# papilio_cam_board.net
KiCad netlist of a schematic drawn in EAGLE
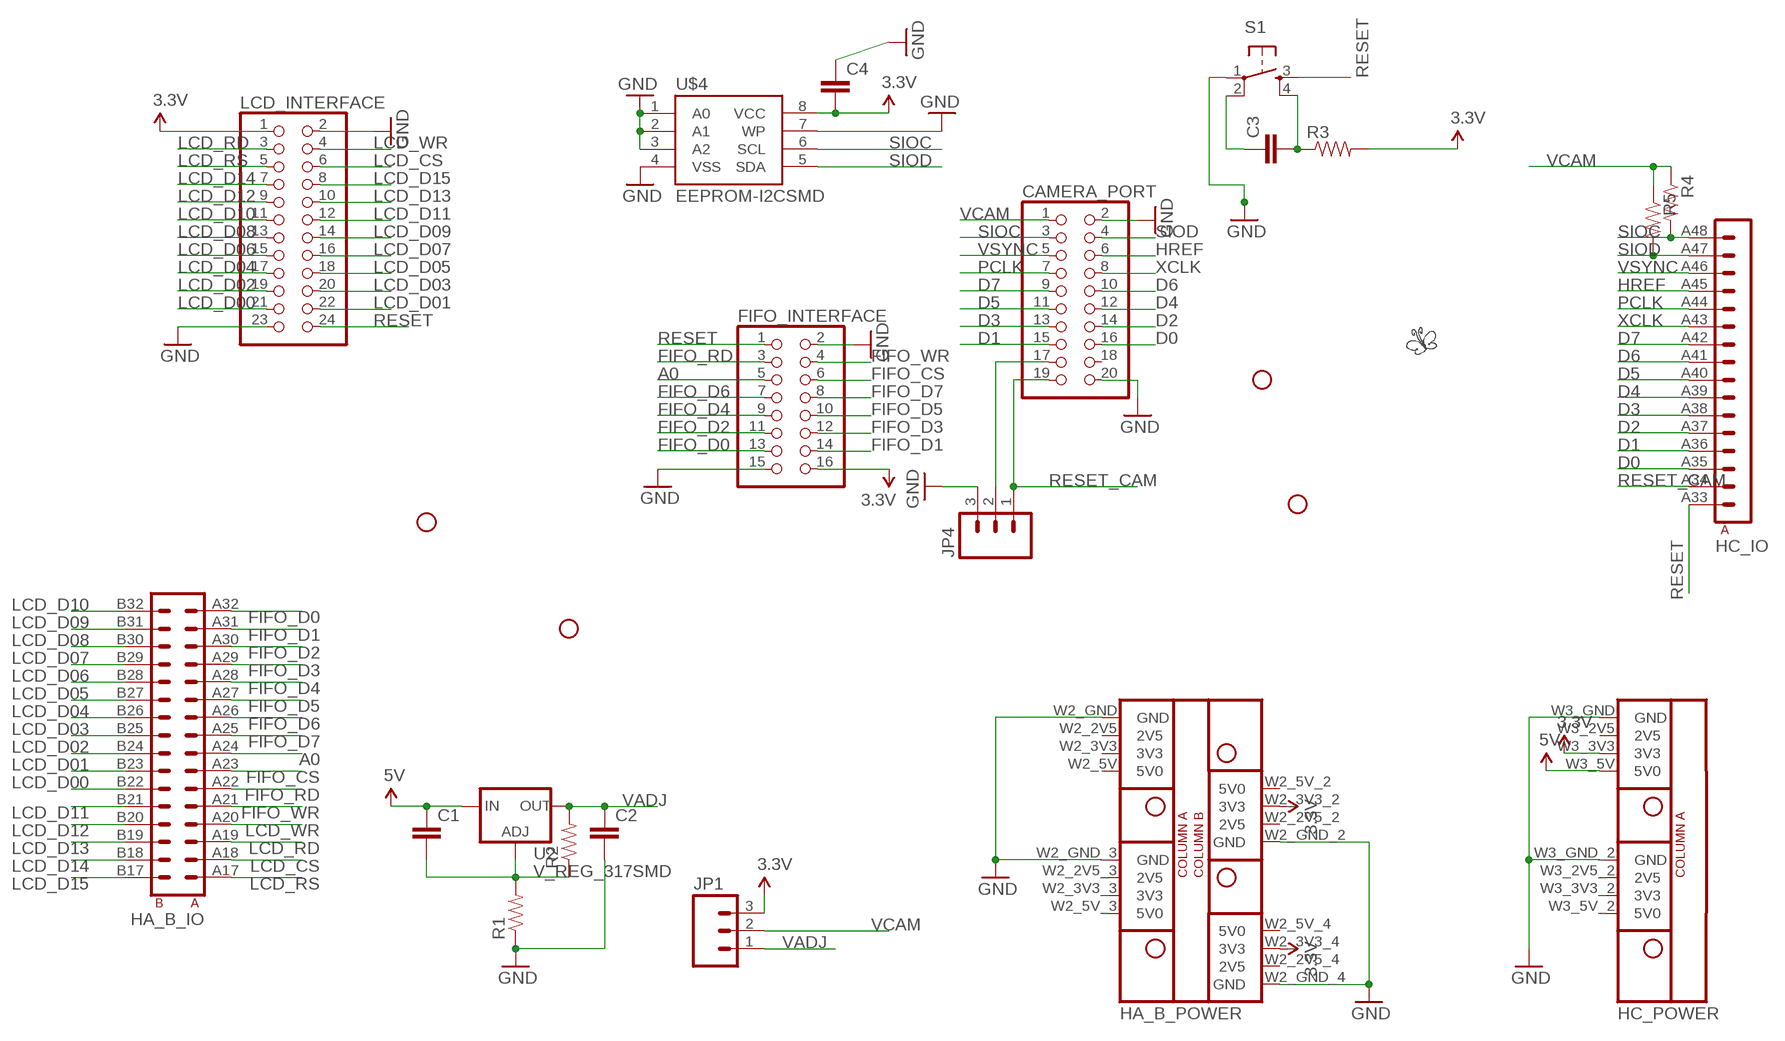
[diagram p0: schematic, sheet 1]

(export (version "E")
  (design (tool "Eeschema 10.0.6"))
  (components
    (comp (ref "C1")
      (value "CAP0805")
      (footprint "eagle-import:0805")
      (libsource (lib "eagle-import") (part "CAP0805"))
    )
    (comp (ref "C2")
      (value "CAP0805")
      (footprint "eagle-import:0805")
      (libsource (lib "eagle-import") (part "CAP0805"))
    )
    (comp (ref "C3")
      (value "CAP0805")
      (footprint "eagle-import:0805")
      (libsource (lib "eagle-import") (part "CAP0805"))
    )
    (comp (ref "C4")
      (value "CAP0805")
      (footprint "eagle-import:0805")
      (libsource (lib "eagle-import") (part "CAP0805"))
    )
    (comp (ref "CAMERA_PORT")
      (value "PINHD-2X10")
      (footprint "eagle-import:2X10")
      (libsource (lib "eagle-import") (part "PINHD-2X10"))
    )
    (comp (ref "FIFO_INTERFACE")
      (value "PINHD-2X8")
      (footprint "eagle-import:2X08")
      (libsource (lib "eagle-import") (part "PINHD-2X8"))
    )
    (comp (ref "H")
      (value "MEGAWING_FULL_P1MEGAWING_P1")
      (footprint "eagle-import:MEGAWING_FULL_NOHOLES_P1")
      (libsource (lib "eagle-import") (part "MEGAWING_FULL_P1MEGAWING_P1"))
    )
    (comp (ref "JP1")
      (value "M03PTH")
      (footprint "eagle-import:1X03")
      (libsource (lib "eagle-import") (part "M03PTH"))
    )
    (comp (ref "JP2")
      (value "STAND-OFF")
      (footprint "eagle-import:STAND-OFF")
      (libsource (lib "eagle-import") (part "STAND-OFF"))
    )
    (comp (ref "JP3")
      (value "STAND-OFF")
      (footprint "eagle-import:STAND-OFF")
      (libsource (lib "eagle-import") (part "STAND-OFF"))
    )
    (comp (ref "JP4")
      (value "M03PTH")
      (footprint "eagle-import:1X03")
      (libsource (lib "eagle-import") (part "M03PTH"))
    )
    (comp (ref "JP5")
      (value "STAND-OFF")
      (footprint "eagle-import:STAND-OFF")
      (libsource (lib "eagle-import") (part "STAND-OFF"))
    )
    (comp (ref "JP7")
      (value "STAND-OFF")
      (footprint "eagle-import:STAND-OFF")
      (libsource (lib "eagle-import") (part "STAND-OFF"))
    )
    (comp (ref "LCD_INTERFACE")
      (value "PINHD-2X12")
      (footprint "eagle-import:2X12")
      (libsource (lib "eagle-import") (part "PINHD-2X12"))
    )
    (comp (ref "LOGO1")
      (value "BUTTERFLY_LOGO")
      (footprint "eagle-import:BUTTERFLY_LOGO")
      (libsource (lib "eagle-import") (part "BUTTERFLY_LOGO"))
    )
    (comp (ref "R1")
      (value "RESISTOR0805-RES")
      (footprint "eagle-import:0805")
      (libsource (lib "eagle-import") (part "RESISTOR0805-RES"))
    )
    (comp (ref "R2")
      (value "RESISTOR0805-RES")
      (footprint "eagle-import:0805")
      (libsource (lib "eagle-import") (part "RESISTOR0805-RES"))
    )
    (comp (ref "R3")
      (value "RESISTOR0805-RES")
      (footprint "eagle-import:0805")
      (libsource (lib "eagle-import") (part "RESISTOR0805-RES"))
    )
    (comp (ref "R4")
      (value "RESISTOR0805-RES")
      (footprint "eagle-import:0805")
      (libsource (lib "eagle-import") (part "RESISTOR0805-RES"))
    )
    (comp (ref "R5")
      (value "RESISTOR0805-RES")
      (footprint "eagle-import:0805")
      (libsource (lib "eagle-import") (part "RESISTOR0805-RES"))
    )
    (comp (ref "S1")
      (value "TAC_SWITCHSMD")
      (footprint "eagle-import:TACTILE_SWITCH_SMD")
      (libsource (lib "eagle-import") (part "TAC_SWITCHSMD"))
    )
    (comp (ref "U$4")
      (value "EEPROM-I2CSMD")
      (footprint "eagle-import:SO08")
      (libsource (lib "eagle-import") (part "EEPROM-I2CSMD"))
    )
    (comp (ref "U2")
      (value "V_REG_317SMD")
      (footprint "eagle-import:SOT223")
      (libsource (lib "eagle-import") (part "V_REG_317SMD"))
    )
  )
  (nets
    (net (code "1") (name "/A0") (class "Default")
      (node (ref "FIFO_INTERFACE") (pin "5") (pinfunction "5_5") (pintype "passive"))
      (node (ref "H") (pin "A24") (pinfunction "A8_A24") (pintype "bidirectional"))
    )
    (net (code "2") (name "/D0") (class "Default")
      (node (ref "CAMERA_PORT") (pin "16") (pinfunction "16_16") (pintype "passive"))
      (node (ref "H") (pin "A35") (pinfunction "A3_A35") (pintype "bidirectional"))
    )
    (net (code "3") (name "/D1") (class "Default")
      (node (ref "CAMERA_PORT") (pin "15") (pinfunction "15_15") (pintype "passive"))
      (node (ref "H") (pin "A36") (pinfunction "A4_A36") (pintype "bidirectional"))
    )
    (net (code "4") (name "/D2") (class "Default")
      (node (ref "CAMERA_PORT") (pin "14") (pinfunction "14_14") (pintype "passive"))
      (node (ref "H") (pin "A37") (pinfunction "A5_A37") (pintype "bidirectional"))
    )
    (net (code "5") (name "/D3") (class "Default")
      (node (ref "CAMERA_PORT") (pin "13") (pinfunction "13_13") (pintype "passive"))
      (node (ref "H") (pin "A38") (pinfunction "A6_A38") (pintype "bidirectional"))
    )
    (net (code "6") (name "/D4") (class "Default")
      (node (ref "CAMERA_PORT") (pin "12") (pinfunction "12_12") (pintype "passive"))
      (node (ref "H") (pin "A39") (pinfunction "A7_A39") (pintype "bidirectional"))
    )
    (net (code "7") (name "/D5") (class "Default")
      (node (ref "CAMERA_PORT") (pin "11") (pinfunction "11_11") (pintype "passive"))
      (node (ref "H") (pin "A40") (pinfunction "A8_A40") (pintype "bidirectional"))
    )
    (net (code "8") (name "/D6") (class "Default")
      (node (ref "CAMERA_PORT") (pin "10") (pinfunction "10_10") (pintype "passive"))
      (node (ref "H") (pin "A41") (pinfunction "A9_A41") (pintype "bidirectional"))
    )
    (net (code "9") (name "/D7") (class "Default")
      (node (ref "CAMERA_PORT") (pin "9") (pinfunction "9_9") (pintype "passive"))
      (node (ref "H") (pin "A42") (pinfunction "A10_A42") (pintype "bidirectional"))
    )
    (net (code "10") (name "/FIFO_CS") (class "Default")
      (node (ref "FIFO_INTERFACE") (pin "6") (pinfunction "6_6") (pintype "passive"))
      (node (ref "H") (pin "A23") (pinfunction "A7_A23") (pintype "bidirectional"))
    )
    (net (code "11") (name "/FIFO_D0") (class "Default")
      (node (ref "FIFO_INTERFACE") (pin "13") (pinfunction "13_13") (pintype "passive"))
      (node (ref "H") (pin "A32") (pinfunction "A16_A32") (pintype "bidirectional"))
    )
    (net (code "12") (name "/FIFO_D1") (class "Default")
      (node (ref "FIFO_INTERFACE") (pin "14") (pinfunction "14_14") (pintype "passive"))
      (node (ref "H") (pin "A31") (pinfunction "A15_A31") (pintype "bidirectional"))
    )
    (net (code "13") (name "/FIFO_D2") (class "Default")
      (node (ref "FIFO_INTERFACE") (pin "11") (pinfunction "11_11") (pintype "passive"))
      (node (ref "H") (pin "A30") (pinfunction "A14_A30") (pintype "bidirectional"))
    )
    (net (code "14") (name "/FIFO_D3") (class "Default")
      (node (ref "FIFO_INTERFACE") (pin "12") (pinfunction "12_12") (pintype "passive"))
      (node (ref "H") (pin "A29") (pinfunction "A13_A29") (pintype "bidirectional"))
    )
    (net (code "15") (name "/FIFO_D4") (class "Default")
      (node (ref "FIFO_INTERFACE") (pin "9") (pinfunction "9_9") (pintype "passive"))
      (node (ref "H") (pin "A28") (pinfunction "A12_A28") (pintype "bidirectional"))
    )
    (net (code "16") (name "/FIFO_D5") (class "Default")
      (node (ref "FIFO_INTERFACE") (pin "10") (pinfunction "10_10") (pintype "passive"))
      (node (ref "H") (pin "A27") (pinfunction "A11_A27") (pintype "bidirectional"))
    )
    (net (code "17") (name "/FIFO_D6") (class "Default")
      (node (ref "FIFO_INTERFACE") (pin "7") (pinfunction "7_7") (pintype "passive"))
      (node (ref "H") (pin "A26") (pinfunction "A10_A26") (pintype "bidirectional"))
    )
    (net (code "18") (name "/FIFO_D7") (class "Default")
      (node (ref "FIFO_INTERFACE") (pin "8") (pinfunction "8_8") (pintype "passive"))
      (node (ref "H") (pin "A25") (pinfunction "A9_A25") (pintype "bidirectional"))
    )
    (net (code "19") (name "/FIFO_RD") (class "Default")
      (node (ref "FIFO_INTERFACE") (pin "3") (pinfunction "3_3") (pintype "passive"))
      (node (ref "H") (pin "A22") (pinfunction "A6_A22") (pintype "bidirectional"))
    )
    (net (code "20") (name "/FIFO_WR") (class "Default")
      (node (ref "FIFO_INTERFACE") (pin "4") (pinfunction "4_4") (pintype "passive"))
      (node (ref "H") (pin "A21") (pinfunction "A5_A21") (pintype "bidirectional"))
    )
    (net (code "21") (name "/HREF") (class "Default")
      (node (ref "CAMERA_PORT") (pin "6") (pinfunction "6_6") (pintype "passive"))
      (node (ref "H") (pin "A45") (pinfunction "A13_A45") (pintype "bidirectional"))
    )
    (net (code "22") (name "/LCD_CS") (class "Default")
      (node (ref "H") (pin "A18") (pinfunction "A2_A18") (pintype "bidirectional"))
      (node (ref "LCD_INTERFACE") (pin "6") (pinfunction "6_6") (pintype "passive"))
    )
    (net (code "23") (name "/LCD_D00") (class "Default")
      (node (ref "H") (pin "B22") (pinfunction "B6_B22") (pintype "bidirectional"))
      (node (ref "LCD_INTERFACE") (pin "21") (pinfunction "21_21") (pintype "passive"))
    )
    (net (code "24") (name "/LCD_D01") (class "Default")
      (node (ref "H") (pin "B23") (pinfunction "B7_B23") (pintype "bidirectional"))
      (node (ref "LCD_INTERFACE") (pin "22") (pinfunction "22_22") (pintype "passive"))
    )
    (net (code "25") (name "/LCD_D02") (class "Default")
      (node (ref "H") (pin "B24") (pinfunction "B8_B24") (pintype "bidirectional"))
      (node (ref "LCD_INTERFACE") (pin "19") (pinfunction "19_19") (pintype "passive"))
    )
    (net (code "26") (name "/LCD_D03") (class "Default")
      (node (ref "H") (pin "B25") (pinfunction "B9_B25") (pintype "bidirectional"))
      (node (ref "LCD_INTERFACE") (pin "20") (pinfunction "20_20") (pintype "passive"))
    )
    (net (code "27") (name "/LCD_D04") (class "Default")
      (node (ref "H") (pin "B26") (pinfunction "B10_B26") (pintype "bidirectional"))
      (node (ref "LCD_INTERFACE") (pin "17") (pinfunction "17_17") (pintype "passive"))
    )
    (net (code "28") (name "/LCD_D05") (class "Default")
      (node (ref "H") (pin "B27") (pinfunction "B11_B27") (pintype "bidirectional"))
      (node (ref "LCD_INTERFACE") (pin "18") (pinfunction "18_18") (pintype "passive"))
    )
    (net (code "29") (name "/LCD_D06") (class "Default")
      (node (ref "H") (pin "B28") (pinfunction "B12_B28") (pintype "bidirectional"))
      (node (ref "LCD_INTERFACE") (pin "15") (pinfunction "15_15") (pintype "passive"))
    )
    (net (code "30") (name "/LCD_D07") (class "Default")
      (node (ref "H") (pin "B29") (pinfunction "B13_B29") (pintype "bidirectional"))
      (node (ref "LCD_INTERFACE") (pin "16") (pinfunction "16_16") (pintype "passive"))
    )
    (net (code "31") (name "/LCD_D08") (class "Default")
      (node (ref "H") (pin "B30") (pinfunction "B14_B30") (pintype "bidirectional"))
      (node (ref "LCD_INTERFACE") (pin "13") (pinfunction "13_13") (pintype "passive"))
    )
    (net (code "32") (name "/LCD_D09") (class "Default")
      (node (ref "H") (pin "B31") (pinfunction "B15_B31") (pintype "bidirectional"))
      (node (ref "LCD_INTERFACE") (pin "14") (pinfunction "14_14") (pintype "passive"))
    )
    (net (code "33") (name "/LCD_D10") (class "Default")
      (node (ref "H") (pin "B32") (pinfunction "B16_B32") (pintype "bidirectional"))
      (node (ref "LCD_INTERFACE") (pin "11") (pinfunction "11_11") (pintype "passive"))
    )
    (net (code "34") (name "/LCD_D11") (class "Default")
      (node (ref "H") (pin "B21") (pinfunction "B5_B21") (pintype "bidirectional"))
      (node (ref "LCD_INTERFACE") (pin "12") (pinfunction "12_12") (pintype "passive"))
    )
    (net (code "35") (name "/LCD_D12") (class "Default")
      (node (ref "H") (pin "B20") (pinfunction "B4_B20") (pintype "bidirectional"))
      (node (ref "LCD_INTERFACE") (pin "9") (pinfunction "9_9") (pintype "passive"))
    )
    (net (code "36") (name "/LCD_D13") (class "Default")
      (node (ref "H") (pin "B19") (pinfunction "B3_B19") (pintype "bidirectional"))
      (node (ref "LCD_INTERFACE") (pin "10") (pinfunction "10_10") (pintype "passive"))
    )
    (net (code "37") (name "/LCD_D14") (class "Default")
      (node (ref "H") (pin "B18") (pinfunction "B2_B18") (pintype "bidirectional"))
      (node (ref "LCD_INTERFACE") (pin "7") (pinfunction "7_7") (pintype "passive"))
    )
    (net (code "38") (name "/LCD_D15") (class "Default")
      (node (ref "H") (pin "B17") (pinfunction "B1_B17") (pintype "bidirectional"))
      (node (ref "LCD_INTERFACE") (pin "8") (pinfunction "8_8") (pintype "passive"))
    )
    (net (code "39") (name "/LCD_RD") (class "Default")
      (node (ref "H") (pin "A19") (pinfunction "A3_A19") (pintype "bidirectional"))
      (node (ref "LCD_INTERFACE") (pin "3") (pinfunction "3_3") (pintype "passive"))
    )
    (net (code "40") (name "/LCD_RS") (class "Default")
      (node (ref "H") (pin "A17") (pinfunction "A1_A17") (pintype "bidirectional"))
      (node (ref "LCD_INTERFACE") (pin "5") (pinfunction "5_5") (pintype "passive"))
    )
    (net (code "41") (name "/LCD_WR") (class "Default")
      (node (ref "H") (pin "A20") (pinfunction "A4_A20") (pintype "bidirectional"))
      (node (ref "LCD_INTERFACE") (pin "4") (pinfunction "4_4") (pintype "passive"))
    )
    (net (code "42") (name "/PCLK") (class "Default")
      (node (ref "CAMERA_PORT") (pin "7") (pinfunction "7_7") (pintype "passive"))
      (node (ref "H") (pin "A44") (pinfunction "A12_A44") (pintype "bidirectional"))
    )
    (net (code "43") (name "/RESET") (class "Default")
      (node (ref "FIFO_INTERFACE") (pin "1") (pinfunction "1_1") (pintype "passive"))
      (node (ref "H") (pin "A33") (pinfunction "A1_A33") (pintype "bidirectional"))
      (node (ref "LCD_INTERFACE") (pin "24") (pinfunction "24_24") (pintype "passive"))
      (node (ref "S1") (pin "3") (pinfunction "3_3") (pintype "passive"))
    )
    (net (code "44") (name "/RESET_CAM") (class "Default")
      (node (ref "CAMERA_PORT") (pin "19") (pinfunction "19_19") (pintype "passive"))
      (node (ref "H") (pin "A34") (pinfunction "A2_A34") (pintype "bidirectional"))
      (node (ref "JP4") (pin "1") (pinfunction "1_1") (pintype "passive"))
    )
    (net (code "45") (name "/SIOC") (class "Default")
      (node (ref "CAMERA_PORT") (pin "3") (pinfunction "3_3") (pintype "passive"))
      (node (ref "H") (pin "A48") (pinfunction "A16_A48") (pintype "bidirectional"))
      (node (ref "R4") (pin "2") (pinfunction "2_2") (pintype "passive"))
      (node (ref "U$4") (pin "6") (pinfunction "SCL_6") (pintype "bidirectional"))
    )
    (net (code "46") (name "/SIOD") (class "Default")
      (node (ref "CAMERA_PORT") (pin "4") (pinfunction "4_4") (pintype "passive"))
      (node (ref "H") (pin "A47") (pinfunction "A15_A47") (pintype "bidirectional"))
      (node (ref "R5") (pin "2") (pinfunction "2_2") (pintype "passive"))
      (node (ref "U$4") (pin "5") (pinfunction "SDA_5") (pintype "bidirectional"))
    )
    (net (code "47") (name "/VADJ") (class "Default")
      (node (ref "C2") (pin "1") (pinfunction "1_1") (pintype "passive"))
      (node (ref "JP1") (pin "1") (pinfunction "1_1") (pintype "passive"))
      (node (ref "R2") (pin "2") (pinfunction "2_2") (pintype "passive"))
      (node (ref "U2") (pin "2") (pinfunction "OUT_2") (pintype "output"))
    )
    (net (code "48") (name "/VCAM") (class "Default")
      (node (ref "CAMERA_PORT") (pin "1") (pinfunction "1_1") (pintype "passive"))
      (node (ref "JP1") (pin "2") (pinfunction "2_2") (pintype "passive"))
      (node (ref "R4") (pin "1") (pinfunction "1_1") (pintype "passive"))
      (node (ref "R5") (pin "1") (pinfunction "1_1") (pintype "passive"))
    )
    (net (code "49") (name "/VSYNC") (class "Default")
      (node (ref "CAMERA_PORT") (pin "5") (pinfunction "5_5") (pintype "passive"))
      (node (ref "H") (pin "A46") (pinfunction "A14_A46") (pintype "bidirectional"))
    )
    (net (code "50") (name "/XCLK") (class "Default")
      (node (ref "CAMERA_PORT") (pin "8") (pinfunction "8_8") (pintype "passive"))
      (node (ref "H") (pin "A43") (pinfunction "A11_A43") (pintype "bidirectional"))
    )
    (net (code "51") (name "3.3V") (class "Default")
      (node (ref "C4") (pin "2") (pinfunction "2_2") (pintype "passive"))
      (node (ref "FIFO_INTERFACE") (pin "16") (pinfunction "16_16") (pintype "passive"))
      (node (ref "H") (pin "W2_3V3_2") (pinfunction "3V3_W2_3V3_2") (pintype "passive"))
      (node (ref "H") (pin "W2_3V3_4") (pinfunction "3V3_W2_3V3_4") (pintype "passive"))
      (node (ref "H") (pin "W3_3V3") (pinfunction "3V3_W3_3V3") (pintype "passive"))
      (node (ref "JP1") (pin "3") (pinfunction "3_3") (pintype "passive"))
      (node (ref "LCD_INTERFACE") (pin "1") (pinfunction "1_1") (pintype "passive"))
      (node (ref "R3") (pin "2") (pinfunction "2_2") (pintype "passive"))
      (node (ref "U$4") (pin "8") (pinfunction "VCC_8") (pintype "power_in"))
    )
    (net (code "52") (name "5V") (class "Default")
      (node (ref "C1") (pin "1") (pinfunction "1_1") (pintype "passive"))
      (node (ref "H") (pin "W3_5V") (pinfunction "5V0_W3_5V") (pintype "passive"))
      (node (ref "U2") (pin "3") (pinfunction "IN_3") (pintype "input"))
    )
    (net (code "53") (name "GND") (class "Default")
      (node (ref "C2") (pin "2") (pinfunction "2_2") (pintype "passive"))
      (node (ref "C4") (pin "1") (pinfunction "1_1") (pintype "passive"))
      (node (ref "CAMERA_PORT") (pin "2") (pinfunction "2_2") (pintype "passive"))
      (node (ref "CAMERA_PORT") (pin "20") (pinfunction "20_20") (pintype "passive"))
      (node (ref "FIFO_INTERFACE") (pin "15") (pinfunction "15_15") (pintype "passive"))
      (node (ref "FIFO_INTERFACE") (pin "2") (pinfunction "2_2") (pintype "passive"))
      (node (ref "H") (pin "W2_GND") (pinfunction "GND_W2_GND") (pintype "power_in"))
      (node (ref "H") (pin "W2_GND_2") (pinfunction "GND_W2_GND_2") (pintype "power_in"))
      (node (ref "H") (pin "W2_GND_3") (pinfunction "GND_W2_GND_3") (pintype "power_in"))
      (node (ref "H") (pin "W2_GND_4") (pinfunction "GND_W2_GND_4") (pintype "power_in"))
      (node (ref "H") (pin "W3_GND") (pinfunction "GND_W3_GND") (pintype "power_in"))
      (node (ref "H") (pin "W3_GND_2") (pinfunction "GND_W3_GND_2") (pintype "power_in"))
      (node (ref "JP4") (pin "3") (pinfunction "3_3") (pintype "passive"))
      (node (ref "LCD_INTERFACE") (pin "2") (pinfunction "2_2") (pintype "passive"))
      (node (ref "LCD_INTERFACE") (pin "23") (pinfunction "23_23") (pintype "passive"))
      (node (ref "R1") (pin "1") (pinfunction "1_1") (pintype "passive"))
      (node (ref "S1") (pin "1") (pinfunction "1_1") (pintype "passive"))
      (node (ref "U$4") (pin "1") (pinfunction "A0_1") (pintype "bidirectional"))
      (node (ref "U$4") (pin "2") (pinfunction "A1_2") (pintype "bidirectional"))
      (node (ref "U$4") (pin "3") (pinfunction "A2_3") (pintype "bidirectional"))
      (node (ref "U$4") (pin "4") (pinfunction "VSS_4") (pintype "power_in"))
      (node (ref "U$4") (pin "7") (pinfunction "WP_7") (pintype "bidirectional"))
    )
    (net (code "54") (name "Net-(C3-Pad1)") (class "Default")
      (node (ref "C3") (pin "1") (pinfunction "1_1") (pintype "passive"))
      (node (ref "S1") (pin "2") (pinfunction "2_2") (pintype "passive"))
    )
    (net (code "55") (name "Net-(C3-Pad2)") (class "Default")
      (node (ref "C3") (pin "2") (pinfunction "2_2") (pintype "passive"))
      (node (ref "R3") (pin "1") (pinfunction "1_1") (pintype "passive"))
      (node (ref "S1") (pin "4") (pinfunction "4_4") (pintype "passive"))
    )
    (net (code "56") (name "Net-(CAMERA_PORT-Pad17)") (class "Default")
      (node (ref "CAMERA_PORT") (pin "17") (pinfunction "17_17") (pintype "passive"))
      (node (ref "JP4") (pin "2") (pinfunction "2_2") (pintype "passive"))
    )
    (net (code "57") (name "Net-(U2-ADJ)") (class "Default")
      (node (ref "C1") (pin "2") (pinfunction "2_2") (pintype "passive"))
      (node (ref "R1") (pin "2") (pinfunction "2_2") (pintype "passive"))
      (node (ref "R2") (pin "1") (pinfunction "1_1") (pintype "passive"))
      (node (ref "U2") (pin "1") (pinfunction "ADJ_1") (pintype "input"))
    )
    (net (code "58") (name "unconnected-(CAMERA_PORT-Pad18)") (class "Default")
      (node (ref "CAMERA_PORT") (pin "18") (pinfunction "18_18") (pintype "passive"))
    )
    (net (code "59") (name "unconnected-(HB-2V5-PadW2_2V5)") (class "Default")
      (node (ref "H") (pin "W2_2V5") (pinfunction "2V5_W2_2V5") (pintype "passive"))
    )
    (net (code "60") (name "unconnected-(HB-2V5-PadW2_2V5_2)") (class "Default")
      (node (ref "H") (pin "W2_2V5_2") (pinfunction "2V5_W2_2V5_2") (pintype "passive"))
    )
    (net (code "61") (name "unconnected-(HB-2V5-PadW2_2V5_3)") (class "Default")
      (node (ref "H") (pin "W2_2V5_3") (pinfunction "2V5_W2_2V5_3") (pintype "passive"))
    )
    (net (code "62") (name "unconnected-(HB-2V5-PadW2_2V5_4)") (class "Default")
      (node (ref "H") (pin "W2_2V5_4") (pinfunction "2V5_W2_2V5_4") (pintype "passive"))
    )
    (net (code "63") (name "unconnected-(HB-3V3-PadW2_3V3)") (class "Default")
      (node (ref "H") (pin "W2_3V3") (pinfunction "3V3_W2_3V3") (pintype "passive"))
    )
    (net (code "64") (name "unconnected-(HB-3V3-PadW2_3V3_3)") (class "Default")
      (node (ref "H") (pin "W2_3V3_3") (pinfunction "3V3_W2_3V3_3") (pintype "passive"))
    )
    (net (code "65") (name "unconnected-(HB-5V0-PadW2_5V)") (class "Default")
      (node (ref "H") (pin "W2_5V") (pinfunction "5V0_W2_5V") (pintype "passive"))
    )
    (net (code "66") (name "unconnected-(HB-5V0-PadW2_5V_2)") (class "Default")
      (node (ref "H") (pin "W2_5V_2") (pinfunction "5V0_W2_5V_2") (pintype "passive"))
    )
    (net (code "67") (name "unconnected-(HB-5V0-PadW2_5V_3)") (class "Default")
      (node (ref "H") (pin "W2_5V_3") (pinfunction "5V0_W2_5V_3") (pintype "passive"))
    )
    (net (code "68") (name "unconnected-(HB-5V0-PadW2_5V_4)") (class "Default")
      (node (ref "H") (pin "W2_5V_4") (pinfunction "5V0_W2_5V_4") (pintype "passive"))
    )
    (net (code "69") (name "unconnected-(HD-2V5-PadW3_2V5)") (class "Default")
      (node (ref "H") (pin "W3_2V5") (pinfunction "2V5_W3_2V5") (pintype "passive"))
    )
    (net (code "70") (name "unconnected-(HD-2V5-PadW3_2V5_2)") (class "Default")
      (node (ref "H") (pin "W3_2V5_2") (pinfunction "2V5_W3_2V5_2") (pintype "passive"))
    )
    (net (code "71") (name "unconnected-(HD-3V3-PadW3_3V3_2)") (class "Default")
      (node (ref "H") (pin "W3_3V3_2") (pinfunction "3V3_W3_3V3_2") (pintype "passive"))
    )
    (net (code "72") (name "unconnected-(HD-5V0-PadW3_5V_2)") (class "Default")
      (node (ref "H") (pin "W3_5V_2") (pinfunction "5V0_W3_5V_2") (pintype "passive"))
    )
  )
)
